# S3860M-S.net
KiCad netlist of a schematic drawn in EAGLE
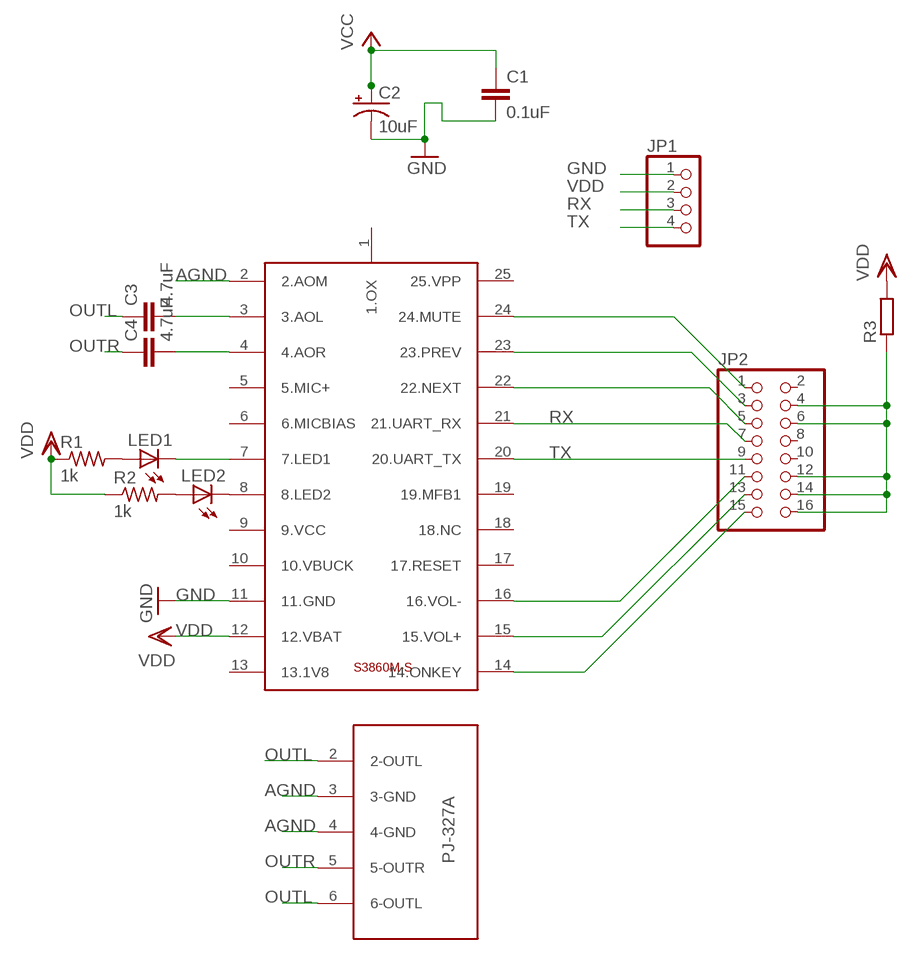
[diagram p0: schematic, sheet 1]

(export (version "E")
  (design (tool "Eeschema 10.0.6"))
  (components
    (comp (ref "C1")
      (value "0.1uF")
      (footprint "eagle-import:1206")
      (libsource (lib "eagle-import") (part "10UF-6.3V-20%(1206)"))
    )
    (comp (ref "C2")
      (value "10uF")
      (footprint "eagle-import:PANASONIC_E")
      (libsource (lib "eagle-import") (part "CAP_POLE"))
    )
    (comp (ref "C3")
      (value "4.7uF")
      (footprint "eagle-import:C1206")
      (libsource (lib "eagle-import") (part "C-EUC1206"))
    )
    (comp (ref "C4")
      (value "4.7uF")
      (footprint "eagle-import:C1206")
      (libsource (lib "eagle-import") (part "C-EUC1206"))
    )
    (comp (ref "JP1")
      (value "PINHD-1X4")
      (footprint "eagle-import:1X04")
      (libsource (lib "eagle-import") (part "PINHD-1X4"))
    )
    (comp (ref "JP2")
      (value "PINHD-2X8")
      (footprint "eagle-import:2X08")
      (libsource (lib "eagle-import") (part "PINHD-2X8"))
    )
    (comp (ref "LED1")
      (value "LEDCHIPLED_0805")
      (footprint "eagle-import:CHIPLED_0805")
      (libsource (lib "eagle-import") (part "LEDCHIPLED_0805"))
    )
    (comp (ref "LED2")
      (value "LEDCHIPLED_0805")
      (footprint "eagle-import:CHIPLED_0805")
      (libsource (lib "eagle-import") (part "LEDCHIPLED_0805"))
    )
    (comp (ref "R1")
      (value "1k")
      (footprint "eagle-import:R1206")
      (libsource (lib "eagle-import") (part "R-US_R1206"))
    )
    (comp (ref "R2")
      (value "1k")
      (footprint "eagle-import:R1206")
      (libsource (lib "eagle-import") (part "R-US_R1206"))
    )
    (comp (ref "R3")
      (value "R-EU_M1206")
      (footprint "eagle-import:M1206")
      (libsource (lib "eagle-import") (part "R-EU_M1206"))
    )
    (comp (ref "U$1")
      (value "S3860M-S")
      (footprint "eagle-import:S3860M-S")
      (libsource (lib "eagle-import") (part "S3860M-S"))
    )
    (comp (ref "U$2")
      (value "PJ-327A")
      (footprint "eagle-import:PJ-327A")
      (libsource (lib "eagle-import") (part "PJ-327A"))
    )
  )
  (nets
    (net (code "1") (name "/AGND") (class "Default")
      (node (ref "U$1") (pin "2") (pinfunction "2.AOM_2") (pintype "bidirectional"))
      (node (ref "U$2") (pin "3") (pinfunction "3-GND_3") (pintype "bidirectional"))
      (node (ref "U$2") (pin "4") (pinfunction "4-GND_4") (pintype "bidirectional"))
    )
    (net (code "2") (name "/OUTL") (class "Default")
      (node (ref "C3") (pin "1") (pinfunction "1_1") (pintype "passive"))
      (node (ref "U$2") (pin "2") (pinfunction "2-OUTL_2") (pintype "bidirectional"))
      (node (ref "U$2") (pin "6") (pinfunction "6-OUTL_6") (pintype "bidirectional"))
    )
    (net (code "3") (name "/OUTR") (class "Default")
      (node (ref "C4") (pin "1") (pinfunction "1_1") (pintype "passive"))
      (node (ref "U$2") (pin "5") (pinfunction "5-OUTR_5") (pintype "bidirectional"))
    )
    (net (code "4") (name "/RX") (class "Default")
      (node (ref "JP1") (pin "3") (pinfunction "3_3") (pintype "passive"))
      (node (ref "JP2") (pin "7") (pinfunction "7_7") (pintype "passive"))
      (node (ref "U$1") (pin "21") (pinfunction "21.UART_RX_21") (pintype "bidirectional"))
    )
    (net (code "5") (name "/TX") (class "Default")
      (node (ref "JP1") (pin "4") (pinfunction "4_4") (pintype "passive"))
      (node (ref "JP2") (pin "9") (pinfunction "9_9") (pintype "passive"))
      (node (ref "U$1") (pin "20") (pinfunction "20.UART_TX_20") (pintype "bidirectional"))
    )
    (net (code "6") (name "GND") (class "Default")
      (node (ref "C1") (pin "2") (pinfunction "2_2") (pintype "passive"))
      (node (ref "C2") (pin "-") (pinfunction "-_-") (pintype "passive"))
      (node (ref "JP1") (pin "1") (pinfunction "1_1") (pintype "passive"))
      (node (ref "U$1") (pin "11") (pinfunction "11.GND_11") (pintype "bidirectional"))
    )
    (net (code "7") (name "Net-(JP2-Pad12)") (class "Default")
      (node (ref "JP2") (pin "12") (pinfunction "12_12") (pintype "passive"))
      (node (ref "JP2") (pin "14") (pinfunction "14_14") (pintype "passive"))
      (node (ref "JP2") (pin "16") (pinfunction "16_16") (pintype "passive"))
      (node (ref "JP2") (pin "4") (pinfunction "4_4") (pintype "passive"))
      (node (ref "JP2") (pin "6") (pinfunction "6_6") (pintype "passive"))
      (node (ref "R3") (pin "1") (pinfunction "1_1") (pintype "passive"))
    )
    (net (code "8") (name "Net-(LED1-PadA)") (class "Default")
      (node (ref "LED1") (pin "A") (pinfunction "A_A") (pintype "passive"))
      (node (ref "R1") (pin "2") (pinfunction "2_2") (pintype "passive"))
    )
    (net (code "9") (name "Net-(LED2-PadA)") (class "Default")
      (node (ref "LED2") (pin "A") (pinfunction "A_A") (pintype "passive"))
      (node (ref "R2") (pin "2") (pinfunction "2_2") (pintype "passive"))
    )
    (net (code "10") (name "Net-(U$1-3.AOL)") (class "Default")
      (node (ref "C3") (pin "2") (pinfunction "2_2") (pintype "passive"))
      (node (ref "U$1") (pin "3") (pinfunction "3.AOL_3") (pintype "bidirectional"))
    )
    (net (code "11") (name "Net-(U$1-4.AOR)") (class "Default")
      (node (ref "C4") (pin "2") (pinfunction "2_2") (pintype "passive"))
      (node (ref "U$1") (pin "4") (pinfunction "4.AOR_4") (pintype "bidirectional"))
    )
    (net (code "12") (name "Net-(U$1-7.LED1)") (class "Default")
      (node (ref "LED1") (pin "C") (pinfunction "C_C") (pintype "passive"))
      (node (ref "U$1") (pin "7") (pinfunction "7.LED1_7") (pintype "bidirectional"))
    )
    (net (code "13") (name "Net-(U$1-8.LED2)") (class "Default")
      (node (ref "LED2") (pin "C") (pinfunction "C_C") (pintype "passive"))
      (node (ref "U$1") (pin "8") (pinfunction "8.LED2_8") (pintype "bidirectional"))
    )
    (net (code "14") (name "Net-(U$1-14.ONKEY)") (class "Default")
      (node (ref "JP2") (pin "15") (pinfunction "15_15") (pintype "passive"))
      (node (ref "U$1") (pin "14") (pinfunction "14.ONKEY_14") (pintype "bidirectional"))
    )
    (net (code "15") (name "Net-(U$1-15.VOL+)") (class "Default")
      (node (ref "JP2") (pin "13") (pinfunction "13_13") (pintype "passive"))
      (node (ref "U$1") (pin "15") (pinfunction "15.VOL+_15") (pintype "bidirectional"))
    )
    (net (code "16") (name "Net-(U$1-16.VOL-)") (class "Default")
      (node (ref "JP2") (pin "11") (pinfunction "11_11") (pintype "passive"))
      (node (ref "U$1") (pin "16") (pinfunction "16.VOL-_16") (pintype "bidirectional"))
    )
    (net (code "17") (name "Net-(U$1-22.NEXT)") (class "Default")
      (node (ref "JP2") (pin "5") (pinfunction "5_5") (pintype "passive"))
      (node (ref "U$1") (pin "22") (pinfunction "22.NEXT_22") (pintype "bidirectional"))
    )
    (net (code "18") (name "Net-(U$1-23.PREV)") (class "Default")
      (node (ref "JP2") (pin "3") (pinfunction "3_3") (pintype "passive"))
      (node (ref "U$1") (pin "23") (pinfunction "23.PREV_23") (pintype "bidirectional"))
    )
    (net (code "19") (name "Net-(U$1-24.MUTE)") (class "Default")
      (node (ref "JP2") (pin "1") (pinfunction "1_1") (pintype "passive"))
      (node (ref "U$1") (pin "24") (pinfunction "24.MUTE_24") (pintype "bidirectional"))
    )
    (net (code "20") (name "VCC") (class "Default")
      (node (ref "C1") (pin "1") (pinfunction "1_1") (pintype "passive"))
      (node (ref "C2") (pin "+") (pinfunction "+_+") (pintype "passive"))
    )
    (net (code "21") (name "VDD") (class "Default")
      (node (ref "JP1") (pin "2") (pinfunction "2_2") (pintype "passive"))
      (node (ref "R1") (pin "1") (pinfunction "1_1") (pintype "passive"))
      (node (ref "R2") (pin "1") (pinfunction "1_1") (pintype "passive"))
      (node (ref "R3") (pin "2") (pinfunction "2_2") (pintype "passive"))
      (node (ref "U$1") (pin "12") (pinfunction "12.VBAT_12") (pintype "bidirectional"))
    )
    (net (code "22") (name "unconnected-(JP2-Pad2)") (class "Default")
      (node (ref "JP2") (pin "2") (pinfunction "2_2") (pintype "passive"))
    )
    (net (code "23") (name "unconnected-(JP2-Pad8)") (class "Default")
      (node (ref "JP2") (pin "8") (pinfunction "8_8") (pintype "passive"))
    )
    (net (code "24") (name "unconnected-(JP2-Pad10)") (class "Default")
      (node (ref "JP2") (pin "10") (pinfunction "10_10") (pintype "passive"))
    )
    (net (code "25") (name "unconnected-(U$1-1.OX-Pad1)") (class "Default")
      (node (ref "U$1") (pin "1") (pinfunction "1.OX_1") (pintype "bidirectional"))
    )
    (net (code "26") (name "unconnected-(U$1-5.MIC+-Pad5)") (class "Default")
      (node (ref "U$1") (pin "5") (pinfunction "5.MIC+_5") (pintype "bidirectional"))
    )
    (net (code "27") (name "unconnected-(U$1-6.MICBIAS-Pad6)") (class "Default")
      (node (ref "U$1") (pin "6") (pinfunction "6.MICBIAS_6") (pintype "bidirectional"))
    )
    (net (code "28") (name "unconnected-(U$1-9.VCC-Pad9)") (class "Default")
      (node (ref "U$1") (pin "9") (pinfunction "9.VCC_9") (pintype "bidirectional"))
    )
    (net (code "29") (name "unconnected-(U$1-10.VBUCK-Pad10)") (class "Default")
      (node (ref "U$1") (pin "10") (pinfunction "10.VBUCK_10") (pintype "bidirectional"))
    )
    (net (code "30") (name "unconnected-(U$1-13.1V8-Pad13)") (class "Default")
      (node (ref "U$1") (pin "13") (pinfunction "13.1V8_13") (pintype "bidirectional"))
    )
    (net (code "31") (name "unconnected-(U$1-17.RESET-Pad17)") (class "Default")
      (node (ref "U$1") (pin "17") (pinfunction "17.RESET_17") (pintype "bidirectional"))
    )
    (net (code "32") (name "unconnected-(U$1-18.NC-Pad18)") (class "Default")
      (node (ref "U$1") (pin "18") (pinfunction "18.NC_18") (pintype "bidirectional"))
    )
    (net (code "33") (name "unconnected-(U$1-19.MFB1-Pad19)") (class "Default")
      (node (ref "U$1") (pin "19") (pinfunction "19.MFB1_19") (pintype "bidirectional"))
    )
    (net (code "34") (name "unconnected-(U$1-25.VPP-Pad25)") (class "Default")
      (node (ref "U$1") (pin "25") (pinfunction "25.VPP_25") (pintype "bidirectional"))
    )
  )
)
